# M223B.net
KiCad netlist of a schematic drawn in EAGLE
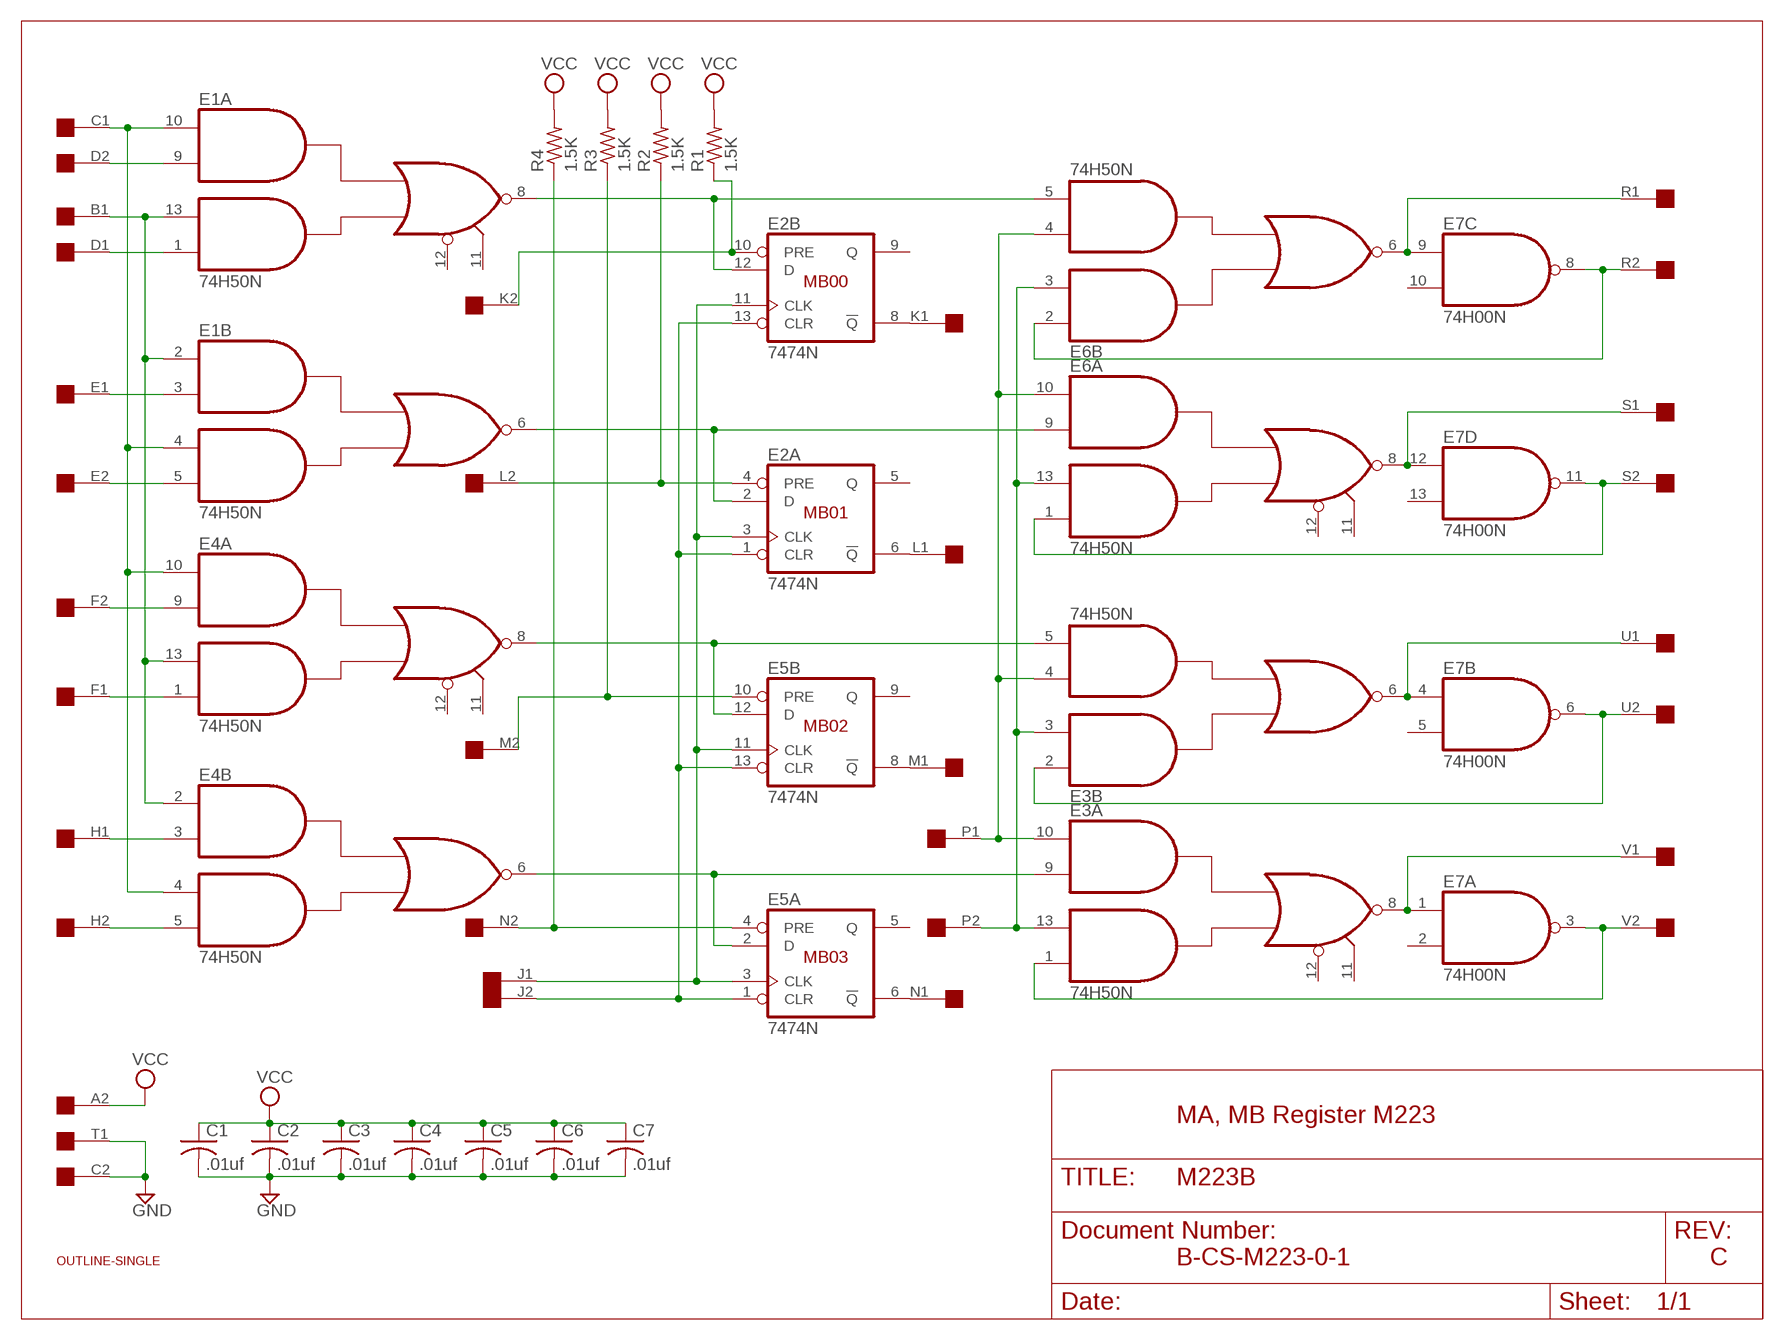
[diagram p0: schematic, sheet 1]

(export (version "E")
  (design (tool "Eeschema 10.0.6"))
  (components
    (comp (ref "C1")
      (value ".01uf")
      (footprint "eagle-import:C050-025X075")
      (libsource (lib "eagle-import") (part "C-US050-025X075"))
    )
    (comp (ref "C2")
      (value ".01uf")
      (footprint "eagle-import:C050-025X075")
      (libsource (lib "eagle-import") (part "C-US050-025X075"))
    )
    (comp (ref "C3")
      (value ".01uf")
      (footprint "eagle-import:C050-025X075")
      (libsource (lib "eagle-import") (part "C-US050-025X075"))
    )
    (comp (ref "C4")
      (value ".01uf")
      (footprint "eagle-import:C050-025X075")
      (libsource (lib "eagle-import") (part "C-US050-025X075"))
    )
    (comp (ref "C5")
      (value ".01uf")
      (footprint "eagle-import:C050-025X075")
      (libsource (lib "eagle-import") (part "C-US050-025X075"))
    )
    (comp (ref "C6")
      (value ".01uf")
      (footprint "eagle-import:C050-025X075")
      (libsource (lib "eagle-import") (part "C-US050-025X075"))
    )
    (comp (ref "C7")
      (value ".01uf")
      (footprint "eagle-import:C050-025X075")
      (libsource (lib "eagle-import") (part "C-US050-025X075"))
    )
    (comp (ref "E1")
      (value "74H50N")
      (footprint "eagle-import:DIL14")
      (libsource (lib "eagle-import") (part "7450N"))
    )
    (comp (ref "E2")
      (value "7474N")
      (footprint "eagle-import:DIL14")
      (libsource (lib "eagle-import") (part "7474NS"))
    )
    (comp (ref "E3")
      (value "74H50N")
      (footprint "eagle-import:DIL14")
      (libsource (lib "eagle-import") (part "7450N"))
    )
    (comp (ref "E4")
      (value "74H50N")
      (footprint "eagle-import:DIL14")
      (libsource (lib "eagle-import") (part "7450N"))
    )
    (comp (ref "E5")
      (value "7474N")
      (footprint "eagle-import:DIL14")
      (libsource (lib "eagle-import") (part "7474NS"))
    )
    (comp (ref "E6")
      (value "74H50N")
      (footprint "eagle-import:DIL14")
      (libsource (lib "eagle-import") (part "7450N"))
    )
    (comp (ref "E7")
      (value "74H00N")
      (footprint "eagle-import:DIL14")
      (libsource (lib "eagle-import") (part "7400N"))
    )
    (comp (ref "R1")
      (value "1.5K")
      (footprint "eagle-import:0207_10")
      (libsource (lib "eagle-import") (part "R-US_0207/10"))
    )
    (comp (ref "R2")
      (value "1.5K")
      (footprint "eagle-import:0207_10")
      (libsource (lib "eagle-import") (part "R-US_0207/10"))
    )
    (comp (ref "R3")
      (value "1.5K")
      (footprint "eagle-import:0207_10")
      (libsource (lib "eagle-import") (part "R-US_0207/10"))
    )
    (comp (ref "R4")
      (value "1.5K")
      (footprint "eagle-import:0207_10")
      (libsource (lib "eagle-import") (part "R-US_0207/10"))
    )
    (comp (ref "U$1")
      (value "OUTLINE-SINGLE")
      (footprint "eagle-import:SINGLE")
      (libsource (lib "eagle-import") (part "OUTLINE-SINGLE"))
    )
    (comp (ref "U$4")
      (value "SINGLE")
      (footprint "eagle-import:EDGE-CON2")
      (libsource (lib "eagle-import") (part "SINGLE"))
    )
  )
  (nets
    (net (code "1") (name "GND") (class "Default")
      (node (ref "C1") (pin "2") (pinfunction "2_2") (pintype "passive"))
      (node (ref "C2") (pin "2") (pinfunction "2_2") (pintype "passive"))
      (node (ref "C3") (pin "2") (pinfunction "2_2") (pintype "passive"))
      (node (ref "C4") (pin "2") (pinfunction "2_2") (pintype "passive"))
      (node (ref "C5") (pin "2") (pinfunction "2_2") (pintype "passive"))
      (node (ref "C6") (pin "2") (pinfunction "2_2") (pintype "passive"))
      (node (ref "C7") (pin "2") (pinfunction "2_2") (pintype "passive"))
      (node (ref "U$4") (pin "C2") (pinfunction "1_C2") (pintype "bidirectional"))
      (node (ref "U$4") (pin "T1") (pinfunction "1_T1") (pintype "bidirectional"))
    )
    (net (code "2") (name "Net-(E1A-I1)") (class "Default")
      (node (ref "E1") (pin "10") (pinfunction "I1_10") (pintype "input"))
      (node (ref "E1") (pin "4") (pinfunction "I3_4") (pintype "input"))
      (node (ref "E4") (pin "10") (pinfunction "I1_10") (pintype "input"))
      (node (ref "E4") (pin "4") (pinfunction "I3_4") (pintype "input"))
      (node (ref "U$4") (pin "C1") (pinfunction "1_C1") (pintype "bidirectional"))
    )
    (net (code "3") (name "Net-(E1A-I2)") (class "Default")
      (node (ref "E1") (pin "9") (pinfunction "I2_9") (pintype "input"))
      (node (ref "U$4") (pin "D2") (pinfunction "1_D2") (pintype "bidirectional"))
    )
    (net (code "4") (name "Net-(E1A-I3)") (class "Default")
      (node (ref "E1") (pin "13") (pinfunction "I3_13") (pintype "input"))
      (node (ref "E1") (pin "2") (pinfunction "I1_2") (pintype "input"))
      (node (ref "E4") (pin "13") (pinfunction "I3_13") (pintype "input"))
      (node (ref "E4") (pin "2") (pinfunction "I1_2") (pintype "input"))
      (node (ref "U$4") (pin "B1") (pinfunction "1_B1") (pintype "bidirectional"))
    )
    (net (code "5") (name "Net-(E1A-I4)") (class "Default")
      (node (ref "E1") (pin "1") (pinfunction "I4_1") (pintype "input"))
      (node (ref "U$4") (pin "D1") (pinfunction "1_D1") (pintype "bidirectional"))
    )
    (net (code "6") (name "Net-(E1A-O)") (class "Default")
      (node (ref "E1") (pin "8") (pinfunction "O_8") (pintype "output"))
      (node (ref "E2") (pin "12") (pinfunction "D_12") (pintype "input"))
      (node (ref "E6") (pin "5") (pinfunction "I4_5") (pintype "input"))
    )
    (net (code "7") (name "Net-(E1B-I2)") (class "Default")
      (node (ref "E1") (pin "3") (pinfunction "I2_3") (pintype "input"))
      (node (ref "U$4") (pin "E1") (pinfunction "1_E1") (pintype "bidirectional"))
    )
    (net (code "8") (name "Net-(E1B-I4)") (class "Default")
      (node (ref "E1") (pin "5") (pinfunction "I4_5") (pintype "input"))
      (node (ref "U$4") (pin "E2") (pinfunction "1_E2") (pintype "bidirectional"))
    )
    (net (code "9") (name "Net-(E1B-O)") (class "Default")
      (node (ref "E1") (pin "6") (pinfunction "O_6") (pintype "output"))
      (node (ref "E2") (pin "2") (pinfunction "D_2") (pintype "input"))
      (node (ref "E6") (pin "9") (pinfunction "I2_9") (pintype "input"))
    )
    (net (code "10") (name "Net-(E2A-CLK)") (class "Default")
      (node (ref "E2") (pin "11") (pinfunction "CLK_11") (pintype "input"))
      (node (ref "E2") (pin "3") (pinfunction "CLK_3") (pintype "input"))
      (node (ref "E5") (pin "11") (pinfunction "CLK_11") (pintype "input"))
      (node (ref "E5") (pin "3") (pinfunction "CLK_3") (pintype "input"))
      (node (ref "U$4") (pin "J1") (pinfunction "1_J1") (pintype "bidirectional"))
    )
    (net (code "11") (name "Net-(E2A-CLR)") (class "Default")
      (node (ref "E2") (pin "1") (pinfunction "CLR_1") (pintype "input"))
      (node (ref "E2") (pin "13") (pinfunction "CLR_13") (pintype "input"))
      (node (ref "E5") (pin "1") (pinfunction "CLR_1") (pintype "input"))
      (node (ref "E5") (pin "13") (pinfunction "CLR_13") (pintype "input"))
      (node (ref "U$4") (pin "J2") (pinfunction "1_J2") (pintype "bidirectional"))
    )
    (net (code "12") (name "Net-(E2A-PRE)") (class "Default")
      (node (ref "E2") (pin "4") (pinfunction "PRE_4") (pintype "input"))
      (node (ref "R2") (pin "1") (pinfunction "1_1") (pintype "passive"))
      (node (ref "U$4") (pin "L2") (pinfunction "1_L2") (pintype "bidirectional"))
    )
    (net (code "13") (name "Net-(E2A-~{Q})") (class "Default")
      (node (ref "E2") (pin "6") (pinfunction "~{Q}_6") (pintype "output"))
      (node (ref "U$4") (pin "L1") (pinfunction "1_L1") (pintype "bidirectional"))
    )
    (net (code "14") (name "Net-(E2B-PRE)") (class "Default")
      (node (ref "E2") (pin "10") (pinfunction "PRE_10") (pintype "input"))
      (node (ref "R1") (pin "1") (pinfunction "1_1") (pintype "passive"))
      (node (ref "U$4") (pin "K2") (pinfunction "1_K2") (pintype "bidirectional"))
    )
    (net (code "15") (name "Net-(E2B-~{Q})") (class "Default")
      (node (ref "E2") (pin "8") (pinfunction "~{Q}_8") (pintype "output"))
      (node (ref "U$4") (pin "K1") (pinfunction "1_K1") (pintype "bidirectional"))
    )
    (net (code "16") (name "Net-(E3A-I1)") (class "Default")
      (node (ref "E3") (pin "10") (pinfunction "I1_10") (pintype "input"))
      (node (ref "E3") (pin "4") (pinfunction "I3_4") (pintype "input"))
      (node (ref "E6") (pin "10") (pinfunction "I1_10") (pintype "input"))
      (node (ref "E6") (pin "4") (pinfunction "I3_4") (pintype "input"))
      (node (ref "U$4") (pin "P1") (pinfunction "1_P1") (pintype "bidirectional"))
    )
    (net (code "17") (name "Net-(E3A-I2)") (class "Default")
      (node (ref "E3") (pin "9") (pinfunction "I2_9") (pintype "input"))
      (node (ref "E4") (pin "6") (pinfunction "O_6") (pintype "output"))
      (node (ref "E5") (pin "2") (pinfunction "D_2") (pintype "input"))
    )
    (net (code "18") (name "Net-(E3A-I3)") (class "Default")
      (node (ref "E3") (pin "13") (pinfunction "I3_13") (pintype "input"))
      (node (ref "E3") (pin "3") (pinfunction "I2_3") (pintype "input"))
      (node (ref "E6") (pin "13") (pinfunction "I3_13") (pintype "input"))
      (node (ref "E6") (pin "3") (pinfunction "I2_3") (pintype "input"))
      (node (ref "U$4") (pin "P2") (pinfunction "1_P2") (pintype "bidirectional"))
    )
    (net (code "19") (name "Net-(E3A-I4)") (class "Default")
      (node (ref "E3") (pin "1") (pinfunction "I4_1") (pintype "input"))
      (node (ref "E7") (pin "3") (pinfunction "O_3") (pintype "output"))
      (node (ref "U$4") (pin "V2") (pinfunction "1_V2") (pintype "bidirectional"))
    )
    (net (code "20") (name "Net-(E3A-O)") (class "Default")
      (node (ref "E3") (pin "8") (pinfunction "O_8") (pintype "output"))
      (node (ref "E7") (pin "1") (pinfunction "I0_1") (pintype "input"))
      (node (ref "U$4") (pin "V1") (pinfunction "1_V1") (pintype "bidirectional"))
    )
    (net (code "21") (name "Net-(E3B-I1)") (class "Default")
      (node (ref "E3") (pin "2") (pinfunction "I1_2") (pintype "input"))
      (node (ref "E7") (pin "6") (pinfunction "O_6") (pintype "output"))
      (node (ref "U$4") (pin "U2") (pinfunction "1_U2") (pintype "bidirectional"))
    )
    (net (code "22") (name "Net-(E3B-I4)") (class "Default")
      (node (ref "E3") (pin "5") (pinfunction "I4_5") (pintype "input"))
      (node (ref "E4") (pin "8") (pinfunction "O_8") (pintype "output"))
      (node (ref "E5") (pin "12") (pinfunction "D_12") (pintype "input"))
    )
    (net (code "23") (name "Net-(E3B-O)") (class "Default")
      (node (ref "E3") (pin "6") (pinfunction "O_6") (pintype "output"))
      (node (ref "E7") (pin "4") (pinfunction "I0_4") (pintype "input"))
      (node (ref "U$4") (pin "U1") (pinfunction "1_U1") (pintype "bidirectional"))
    )
    (net (code "24") (name "Net-(E4A-I2)") (class "Default")
      (node (ref "E4") (pin "9") (pinfunction "I2_9") (pintype "input"))
      (node (ref "U$4") (pin "F2") (pinfunction "1_F2") (pintype "bidirectional"))
    )
    (net (code "25") (name "Net-(E4A-I4)") (class "Default")
      (node (ref "E4") (pin "1") (pinfunction "I4_1") (pintype "input"))
      (node (ref "U$4") (pin "F1") (pinfunction "1_F1") (pintype "bidirectional"))
    )
    (net (code "26") (name "Net-(E4B-I2)") (class "Default")
      (node (ref "E4") (pin "3") (pinfunction "I2_3") (pintype "input"))
      (node (ref "U$4") (pin "H1") (pinfunction "1_H1") (pintype "bidirectional"))
    )
    (net (code "27") (name "Net-(E4B-I4)") (class "Default")
      (node (ref "E4") (pin "5") (pinfunction "I4_5") (pintype "input"))
      (node (ref "U$4") (pin "H2") (pinfunction "1_H2") (pintype "bidirectional"))
    )
    (net (code "28") (name "Net-(E5A-PRE)") (class "Default")
      (node (ref "E5") (pin "4") (pinfunction "PRE_4") (pintype "input"))
      (node (ref "R4") (pin "1") (pinfunction "1_1") (pintype "passive"))
      (node (ref "U$4") (pin "N2") (pinfunction "1_N2") (pintype "bidirectional"))
    )
    (net (code "29") (name "Net-(E5A-~{Q})") (class "Default")
      (node (ref "E5") (pin "6") (pinfunction "~{Q}_6") (pintype "output"))
      (node (ref "U$4") (pin "N1") (pinfunction "1_N1") (pintype "bidirectional"))
    )
    (net (code "30") (name "Net-(E5B-PRE)") (class "Default")
      (node (ref "E5") (pin "10") (pinfunction "PRE_10") (pintype "input"))
      (node (ref "R3") (pin "1") (pinfunction "1_1") (pintype "passive"))
      (node (ref "U$4") (pin "M2") (pinfunction "1_M2") (pintype "bidirectional"))
    )
    (net (code "31") (name "Net-(E5B-~{Q})") (class "Default")
      (node (ref "E5") (pin "8") (pinfunction "~{Q}_8") (pintype "output"))
      (node (ref "U$4") (pin "M1") (pinfunction "1_M1") (pintype "bidirectional"))
    )
    (net (code "32") (name "Net-(E6A-I4)") (class "Default")
      (node (ref "E6") (pin "1") (pinfunction "I4_1") (pintype "input"))
      (node (ref "E7") (pin "11") (pinfunction "O_11") (pintype "output"))
      (node (ref "U$4") (pin "S2") (pinfunction "1_S2") (pintype "bidirectional"))
    )
    (net (code "33") (name "Net-(E6A-O)") (class "Default")
      (node (ref "E6") (pin "8") (pinfunction "O_8") (pintype "output"))
      (node (ref "E7") (pin "12") (pinfunction "I0_12") (pintype "input"))
      (node (ref "U$4") (pin "S1") (pinfunction "1_S1") (pintype "bidirectional"))
    )
    (net (code "34") (name "Net-(E6B-I1)") (class "Default")
      (node (ref "E6") (pin "2") (pinfunction "I1_2") (pintype "input"))
      (node (ref "E7") (pin "8") (pinfunction "O_8") (pintype "output"))
      (node (ref "U$4") (pin "R2") (pinfunction "1_R2") (pintype "bidirectional"))
    )
    (net (code "35") (name "Net-(E6B-O)") (class "Default")
      (node (ref "E6") (pin "6") (pinfunction "O_6") (pintype "output"))
      (node (ref "E7") (pin "9") (pinfunction "I0_9") (pintype "input"))
      (node (ref "U$4") (pin "R1") (pinfunction "1_R1") (pintype "bidirectional"))
    )
    (net (code "36") (name "VCC") (class "Default")
      (node (ref "C1") (pin "1") (pinfunction "1_1") (pintype "passive"))
      (node (ref "C2") (pin "1") (pinfunction "1_1") (pintype "passive"))
      (node (ref "C3") (pin "1") (pinfunction "1_1") (pintype "passive"))
      (node (ref "C4") (pin "1") (pinfunction "1_1") (pintype "passive"))
      (node (ref "C5") (pin "1") (pinfunction "1_1") (pintype "passive"))
      (node (ref "C6") (pin "1") (pinfunction "1_1") (pintype "passive"))
      (node (ref "C7") (pin "1") (pinfunction "1_1") (pintype "passive"))
      (node (ref "R1") (pin "2") (pinfunction "2_2") (pintype "passive"))
      (node (ref "R2") (pin "2") (pinfunction "2_2") (pintype "passive"))
      (node (ref "R3") (pin "2") (pinfunction "2_2") (pintype "passive"))
      (node (ref "R4") (pin "2") (pinfunction "2_2") (pintype "passive"))
      (node (ref "U$4") (pin "A2") (pinfunction "1_A2") (pintype "bidirectional"))
    )
    (net (code "37") (name "unconnected-(E1A-I5-Pad12)") (class "Default")
      (node (ref "E1") (pin "12") (pinfunction "I5_12") (pintype "passive"))
    )
    (net (code "38") (name "unconnected-(E1A-I6-Pad11)") (class "Default")
      (node (ref "E1") (pin "11") (pinfunction "I6_11") (pintype "passive"))
    )
    (net (code "39") (name "unconnected-(E2A-Q-Pad5)") (class "Default")
      (node (ref "E2") (pin "5") (pinfunction "Q_5") (pintype "output"))
    )
    (net (code "40") (name "unconnected-(E2B-Q-Pad9)") (class "Default")
      (node (ref "E2") (pin "9") (pinfunction "Q_9") (pintype "output"))
    )
    (net (code "41") (name "unconnected-(E3A-I5-Pad12)") (class "Default")
      (node (ref "E3") (pin "12") (pinfunction "I5_12") (pintype "passive"))
    )
    (net (code "42") (name "unconnected-(E3A-I6-Pad11)") (class "Default")
      (node (ref "E3") (pin "11") (pinfunction "I6_11") (pintype "passive"))
    )
    (net (code "43") (name "unconnected-(E4A-I5-Pad12)") (class "Default")
      (node (ref "E4") (pin "12") (pinfunction "I5_12") (pintype "passive"))
    )
    (net (code "44") (name "unconnected-(E4A-I6-Pad11)") (class "Default")
      (node (ref "E4") (pin "11") (pinfunction "I6_11") (pintype "passive"))
    )
    (net (code "45") (name "unconnected-(E5A-Q-Pad5)") (class "Default")
      (node (ref "E5") (pin "5") (pinfunction "Q_5") (pintype "output"))
    )
    (net (code "46") (name "unconnected-(E5B-Q-Pad9)") (class "Default")
      (node (ref "E5") (pin "9") (pinfunction "Q_9") (pintype "output"))
    )
    (net (code "47") (name "unconnected-(E6A-I5-Pad12)") (class "Default")
      (node (ref "E6") (pin "12") (pinfunction "I5_12") (pintype "passive"))
    )
    (net (code "48") (name "unconnected-(E6A-I6-Pad11)") (class "Default")
      (node (ref "E6") (pin "11") (pinfunction "I6_11") (pintype "passive"))
    )
    (net (code "49") (name "unconnected-(E7A-I1-Pad2)") (class "Default")
      (node (ref "E7") (pin "2") (pinfunction "I1_2") (pintype "input"))
    )
    (net (code "50") (name "unconnected-(E7B-I1-Pad5)") (class "Default")
      (node (ref "E7") (pin "5") (pinfunction "I1_5") (pintype "input"))
    )
    (net (code "51") (name "unconnected-(E7C-I1-Pad10)") (class "Default")
      (node (ref "E7") (pin "10") (pinfunction "I1_10") (pintype "input"))
    )
    (net (code "52") (name "unconnected-(E7D-I1-Pad13)") (class "Default")
      (node (ref "E7") (pin "13") (pinfunction "I1_13") (pintype "input"))
    )
  )
)
